# LaunchpadGroveBaseboard.net
KiCad netlist of a schematic drawn in EAGLE
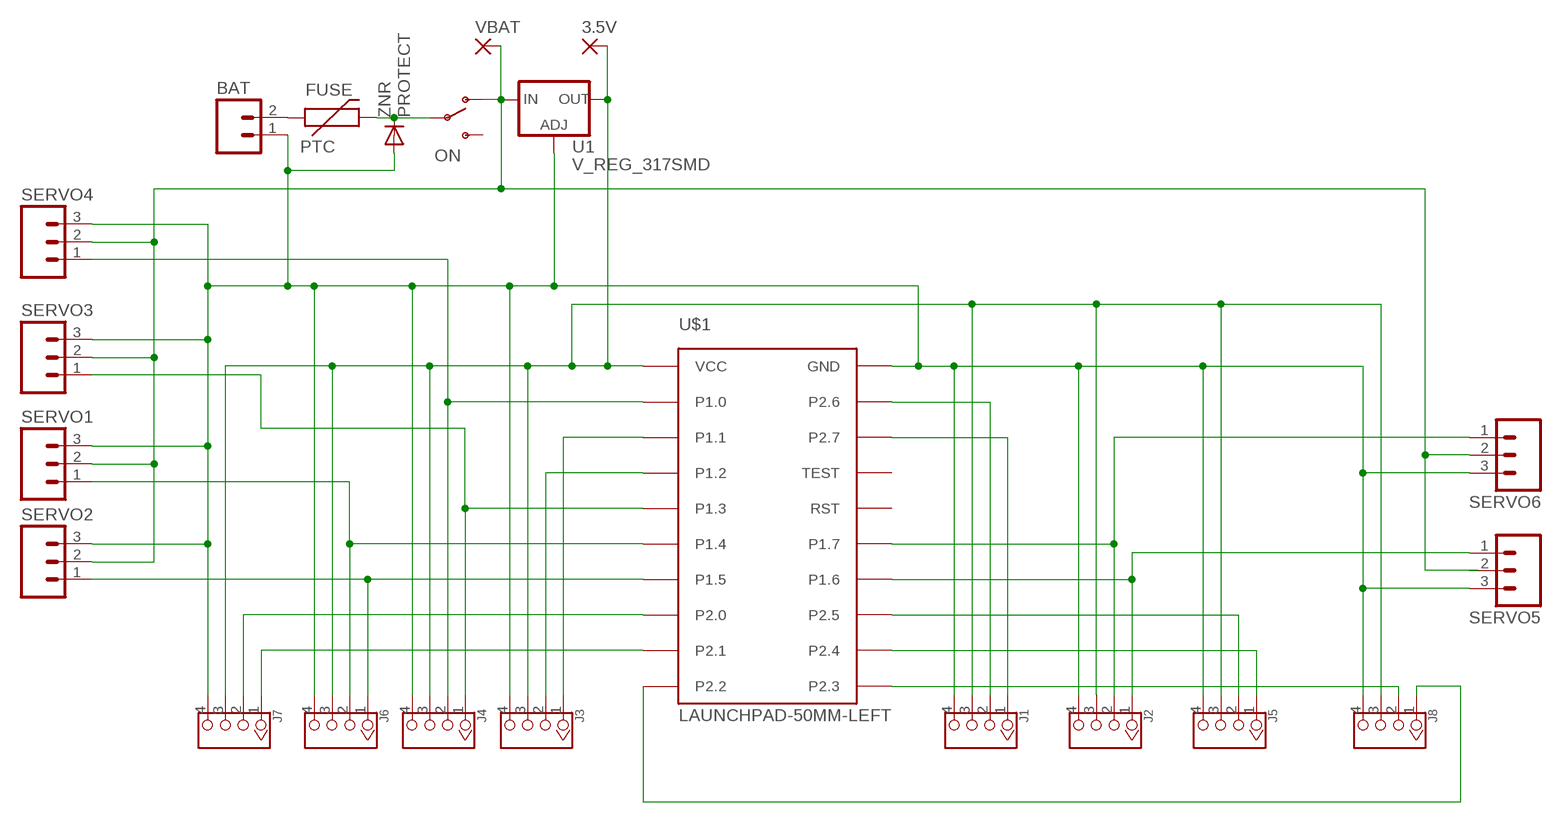
[diagram p0: schematic, sheet 1]

(export (version "E")
  (design (tool "Eeschema 10.0.6"))
  (components
    (comp (ref "3.5V")
      (value "2,15/1,0")
      (footprint "eagle-import:2,15_1,0")
      (libsource (lib "eagle-import") (part "2,15/1,0"))
    )
    (comp (ref "BAT")
      (value "M02PTH")
      (footprint "eagle-import:1X02")
      (libsource (lib "eagle-import") (part "M02PTH"))
    )
    (comp (ref "FUSE")
      (value "PTC")
      (footprint "eagle-import:PTC")
      (libsource (lib "eagle-import") (part "PTCPTH"))
    )
    (comp (ref "J1")
      (value "TWIG-4P-2.0-2.0")
      (footprint "eagle-import:4P-2.0")
      (libsource (lib "eagle-import") (part "TWIG-4P-2.0-2.0"))
    )
    (comp (ref "J2")
      (value "TWIG-4P-2.0-2.0")
      (footprint "eagle-import:4P-2.0")
      (libsource (lib "eagle-import") (part "TWIG-4P-2.0-2.0"))
    )
    (comp (ref "J3")
      (value "TWIG-4P-2.0-2.0")
      (footprint "eagle-import:4P-2.0")
      (libsource (lib "eagle-import") (part "TWIG-4P-2.0-2.0"))
    )
    (comp (ref "J4")
      (value "TWIG-4P-2.0-2.0")
      (footprint "eagle-import:4P-2.0")
      (libsource (lib "eagle-import") (part "TWIG-4P-2.0-2.0"))
    )
    (comp (ref "J5")
      (value "TWIG-4P-2.0-2.0")
      (footprint "eagle-import:4P-2.0")
      (libsource (lib "eagle-import") (part "TWIG-4P-2.0-2.0"))
    )
    (comp (ref "J6")
      (value "TWIG-4P-2.0-2.0")
      (footprint "eagle-import:4P-2.0")
      (libsource (lib "eagle-import") (part "TWIG-4P-2.0-2.0"))
    )
    (comp (ref "J7")
      (value "TWIG-4P-2.0-2.0")
      (footprint "eagle-import:4P-2.0")
      (libsource (lib "eagle-import") (part "TWIG-4P-2.0-2.0"))
    )
    (comp (ref "J8")
      (value "TWIG-4P-2.0-2.0")
      (footprint "eagle-import:4P-2.0")
      (libsource (lib "eagle-import") (part "TWIG-4P-2.0-2.0"))
    )
    (comp (ref "ON")
      (value "SWITCH-SPSTPTH")
      (footprint "eagle-import:SWITCH-SPDT")
      (libsource (lib "eagle-import") (part "SWITCH-SPSTPTH"))
    )
    (comp (ref "SERVO1")
      (value "M03PTH")
      (footprint "eagle-import:1X03")
      (libsource (lib "eagle-import") (part "M03PTH"))
    )
    (comp (ref "SERVO2")
      (value "M03PTH")
      (footprint "eagle-import:1X03")
      (libsource (lib "eagle-import") (part "M03PTH"))
    )
    (comp (ref "SERVO3")
      (value "M03PTH")
      (footprint "eagle-import:1X03")
      (libsource (lib "eagle-import") (part "M03PTH"))
    )
    (comp (ref "SERVO4")
      (value "M03PTH")
      (footprint "eagle-import:1X03")
      (libsource (lib "eagle-import") (part "M03PTH"))
    )
    (comp (ref "SERVO5")
      (value "M03PTH")
      (footprint "eagle-import:1X03")
      (libsource (lib "eagle-import") (part "M03PTH"))
    )
    (comp (ref "SERVO6")
      (value "M03PTH")
      (footprint "eagle-import:1X03")
      (libsource (lib "eagle-import") (part "M03PTH"))
    )
    (comp (ref "U$1")
      (value "LAUNCHPAD-50MM-LEFT")
      (footprint "eagle-import:LAUNCHPAD-50MM-LEFT")
      (libsource (lib "eagle-import") (part "LAUNCHPAD-50MM-LEFT"))
    )
    (comp (ref "U1")
      (value "V_REG_317SMD")
      (footprint "eagle-import:SOT223")
      (libsource (lib "eagle-import") (part "V_REG_317SMD"))
    )
    (comp (ref "VBAT")
      (value "2,15/1,0")
      (footprint "eagle-import:2,15_1,0")
      (libsource (lib "eagle-import") (part "2,15/1,0"))
    )
    (comp (ref "ZNR")
      (value "PROTECT")
      (footprint "eagle-import:DO41-10")
      (libsource (lib "eagle-import") (part "1N4004"))
    )
  )
  (nets
    (net (code "1") (name "Net-(3.5V-P)") (class "Default")
      (node (ref "3.5V") (pin "1") (pinfunction "P_1") (pintype "passive"))
      (node (ref "J1") (pin "3") (pinfunction "3_3") (pintype "bidirectional"))
      (node (ref "J2") (pin "3") (pinfunction "3_3") (pintype "bidirectional"))
      (node (ref "J3") (pin "3") (pinfunction "3_3") (pintype "bidirectional"))
      (node (ref "J4") (pin "3") (pinfunction "3_3") (pintype "bidirectional"))
      (node (ref "J5") (pin "3") (pinfunction "3_3") (pintype "bidirectional"))
      (node (ref "J6") (pin "3") (pinfunction "3_3") (pintype "bidirectional"))
      (node (ref "J7") (pin "3") (pinfunction "3_3") (pintype "bidirectional"))
      (node (ref "J8") (pin "3") (pinfunction "3_3") (pintype "bidirectional"))
      (node (ref "U$1") (pin "VCC") (pinfunction "VCC_VCC") (pintype "power_in"))
      (node (ref "U1") (pin "2") (pinfunction "OUT_2") (pintype "output"))
    )
    (net (code "2") (name "Net-(FUSE-1)") (class "Default")
      (node (ref "BAT") (pin "2") (pinfunction "2_2") (pintype "passive"))
      (node (ref "FUSE") (pin "P$1") (pinfunction "1_P$1") (pintype "bidirectional"))
    )
    (net (code "3") (name "Net-(FUSE-2)") (class "Default")
      (node (ref "FUSE") (pin "P$2") (pinfunction "2_P$2") (pintype "bidirectional"))
      (node (ref "ON") (pin "2") (pinfunction "P_2") (pintype "passive"))
      (node (ref "ZNR") (pin "C") (pinfunction "C_C") (pintype "passive"))
    )
    (net (code "4") (name "Net-(J1-Pad1)") (class "Default")
      (node (ref "J1") (pin "1") (pinfunction "1_1") (pintype "bidirectional"))
      (node (ref "U$1") (pin "P2.7") (pinfunction "P2.7_P2.7") (pintype "bidirectional"))
    )
    (net (code "5") (name "Net-(J1-Pad2)") (class "Default")
      (node (ref "J1") (pin "2") (pinfunction "2_2") (pintype "bidirectional"))
      (node (ref "U$1") (pin "P2.6") (pinfunction "P2.6_P2.6") (pintype "bidirectional"))
    )
    (net (code "6") (name "Net-(J2-Pad1)") (class "Default")
      (node (ref "J2") (pin "1") (pinfunction "1_1") (pintype "bidirectional"))
      (node (ref "SERVO5") (pin "1") (pinfunction "1_1") (pintype "passive"))
      (node (ref "U$1") (pin "P1.6") (pinfunction "P1.6_P1.6") (pintype "bidirectional"))
    )
    (net (code "7") (name "Net-(J2-Pad2)") (class "Default")
      (node (ref "J2") (pin "2") (pinfunction "2_2") (pintype "bidirectional"))
      (node (ref "SERVO6") (pin "1") (pinfunction "1_1") (pintype "passive"))
      (node (ref "U$1") (pin "P1.7") (pinfunction "P1.7_P1.7") (pintype "bidirectional"))
    )
    (net (code "8") (name "Net-(J3-Pad1)") (class "Default")
      (node (ref "J3") (pin "1") (pinfunction "1_1") (pintype "bidirectional"))
      (node (ref "U$1") (pin "P1.1") (pinfunction "P1.1_P1.1") (pintype "bidirectional"))
    )
    (net (code "9") (name "Net-(J3-Pad2)") (class "Default")
      (node (ref "J3") (pin "2") (pinfunction "2_2") (pintype "bidirectional"))
      (node (ref "U$1") (pin "P1.2") (pinfunction "P1.2_P1.2") (pintype "bidirectional"))
    )
    (net (code "10") (name "Net-(J4-Pad1)") (class "Default")
      (node (ref "J4") (pin "1") (pinfunction "1_1") (pintype "bidirectional"))
      (node (ref "SERVO3") (pin "1") (pinfunction "1_1") (pintype "passive"))
      (node (ref "U$1") (pin "P1.3") (pinfunction "P1.3_P1.3") (pintype "bidirectional"))
    )
    (net (code "11") (name "Net-(J4-Pad2)") (class "Default")
      (node (ref "J4") (pin "2") (pinfunction "2_2") (pintype "bidirectional"))
      (node (ref "SERVO4") (pin "1") (pinfunction "1_1") (pintype "passive"))
      (node (ref "U$1") (pin "P1.0") (pinfunction "P1.0_P1.0") (pintype "bidirectional"))
    )
    (net (code "12") (name "Net-(J5-Pad1)") (class "Default")
      (node (ref "J5") (pin "1") (pinfunction "1_1") (pintype "bidirectional"))
      (node (ref "U$1") (pin "P2.4") (pinfunction "P2.4_P2.4") (pintype "bidirectional"))
    )
    (net (code "13") (name "Net-(J5-Pad2)") (class "Default")
      (node (ref "J5") (pin "2") (pinfunction "2_2") (pintype "bidirectional"))
      (node (ref "U$1") (pin "P2.5") (pinfunction "P2.5_P2.5") (pintype "bidirectional"))
    )
    (net (code "14") (name "Net-(J6-Pad1)") (class "Default")
      (node (ref "J6") (pin "1") (pinfunction "1_1") (pintype "bidirectional"))
      (node (ref "SERVO2") (pin "1") (pinfunction "1_1") (pintype "passive"))
      (node (ref "U$1") (pin "P1.5") (pinfunction "P1.5_P1.5") (pintype "bidirectional"))
    )
    (net (code "15") (name "Net-(J6-Pad2)") (class "Default")
      (node (ref "J6") (pin "2") (pinfunction "2_2") (pintype "bidirectional"))
      (node (ref "SERVO1") (pin "1") (pinfunction "1_1") (pintype "passive"))
      (node (ref "U$1") (pin "P1.4") (pinfunction "P1.4_P1.4") (pintype "bidirectional"))
    )
    (net (code "16") (name "Net-(J7-Pad1)") (class "Default")
      (node (ref "J7") (pin "1") (pinfunction "1_1") (pintype "bidirectional"))
      (node (ref "U$1") (pin "P2.1") (pinfunction "P2.1_P2.1") (pintype "bidirectional"))
    )
    (net (code "17") (name "Net-(J7-Pad2)") (class "Default")
      (node (ref "J7") (pin "2") (pinfunction "2_2") (pintype "bidirectional"))
      (node (ref "U$1") (pin "P2.0") (pinfunction "P2.0_P2.0") (pintype "bidirectional"))
    )
    (net (code "18") (name "Net-(J8-Pad1)") (class "Default")
      (node (ref "J8") (pin "1") (pinfunction "1_1") (pintype "bidirectional"))
      (node (ref "U$1") (pin "P2.2") (pinfunction "P2.2_P2.2") (pintype "bidirectional"))
    )
    (net (code "19") (name "Net-(J8-Pad2)") (class "Default")
      (node (ref "J8") (pin "2") (pinfunction "2_2") (pintype "bidirectional"))
      (node (ref "U$1") (pin "P2.3") (pinfunction "P2.3_P2.3") (pintype "bidirectional"))
    )
    (net (code "20") (name "Net-(ON-O)") (class "Default")
      (node (ref "ON") (pin "1") (pinfunction "O_1") (pintype "passive"))
      (node (ref "SERVO1") (pin "2") (pinfunction "2_2") (pintype "passive"))
      (node (ref "SERVO2") (pin "2") (pinfunction "2_2") (pintype "passive"))
      (node (ref "SERVO3") (pin "2") (pinfunction "2_2") (pintype "passive"))
      (node (ref "SERVO4") (pin "2") (pinfunction "2_2") (pintype "passive"))
      (node (ref "SERVO6") (pin "2") (pinfunction "2_2") (pintype "passive"))
      (node (ref "U1") (pin "3") (pinfunction "IN_3") (pintype "input"))
      (node (ref "VBAT") (pin "1") (pinfunction "P_1") (pintype "passive"))
    )
    (net (code "21") (name "Net-(U1-ADJ)") (class "Default")
      (node (ref "BAT") (pin "1") (pinfunction "1_1") (pintype "passive"))
      (node (ref "J1") (pin "4") (pinfunction "4_4") (pintype "bidirectional"))
      (node (ref "J2") (pin "4") (pinfunction "4_4") (pintype "bidirectional"))
      (node (ref "J3") (pin "4") (pinfunction "4_4") (pintype "bidirectional"))
      (node (ref "J4") (pin "4") (pinfunction "4_4") (pintype "bidirectional"))
      (node (ref "J5") (pin "4") (pinfunction "4_4") (pintype "bidirectional"))
      (node (ref "J6") (pin "4") (pinfunction "4_4") (pintype "bidirectional"))
      (node (ref "J7") (pin "4") (pinfunction "4_4") (pintype "bidirectional"))
      (node (ref "J8") (pin "4") (pinfunction "4_4") (pintype "bidirectional"))
      (node (ref "SERVO1") (pin "3") (pinfunction "3_3") (pintype "passive"))
      (node (ref "SERVO2") (pin "3") (pinfunction "3_3") (pintype "passive"))
      (node (ref "SERVO3") (pin "3") (pinfunction "3_3") (pintype "passive"))
      (node (ref "SERVO4") (pin "3") (pinfunction "3_3") (pintype "passive"))
      (node (ref "SERVO5") (pin "3") (pinfunction "3_3") (pintype "passive"))
      (node (ref "SERVO6") (pin "3") (pinfunction "3_3") (pintype "passive"))
      (node (ref "U$1") (pin "GND") (pinfunction "GND_GND") (pintype "power_in"))
      (node (ref "U1") (pin "1") (pinfunction "ADJ_1") (pintype "input"))
      (node (ref "ZNR") (pin "A") (pinfunction "A_A") (pintype "passive"))
    )
    (net (code "22") (name "unconnected-(ON-S-Pad3)") (class "Default")
      (node (ref "ON") (pin "3") (pinfunction "S_3") (pintype "passive"))
    )
    (net (code "23") (name "unconnected-(SERVO5-Pad2)") (class "Default")
      (node (ref "SERVO5") (pin "2") (pinfunction "2_2") (pintype "passive"))
    )
    (net (code "24") (name "unconnected-(U$1-PadRST)") (class "Default")
      (node (ref "U$1") (pin "RST") (pinfunction "RST_RST") (pintype "bidirectional"))
    )
    (net (code "25") (name "unconnected-(U$1-PadTEST)") (class "Default")
      (node (ref "U$1") (pin "TEST") (pinfunction "TEST_TEST") (pintype "bidirectional"))
    )
  )
)
